# secon_analog_in.net
KiCad netlist of a schematic drawn in Altium Designer
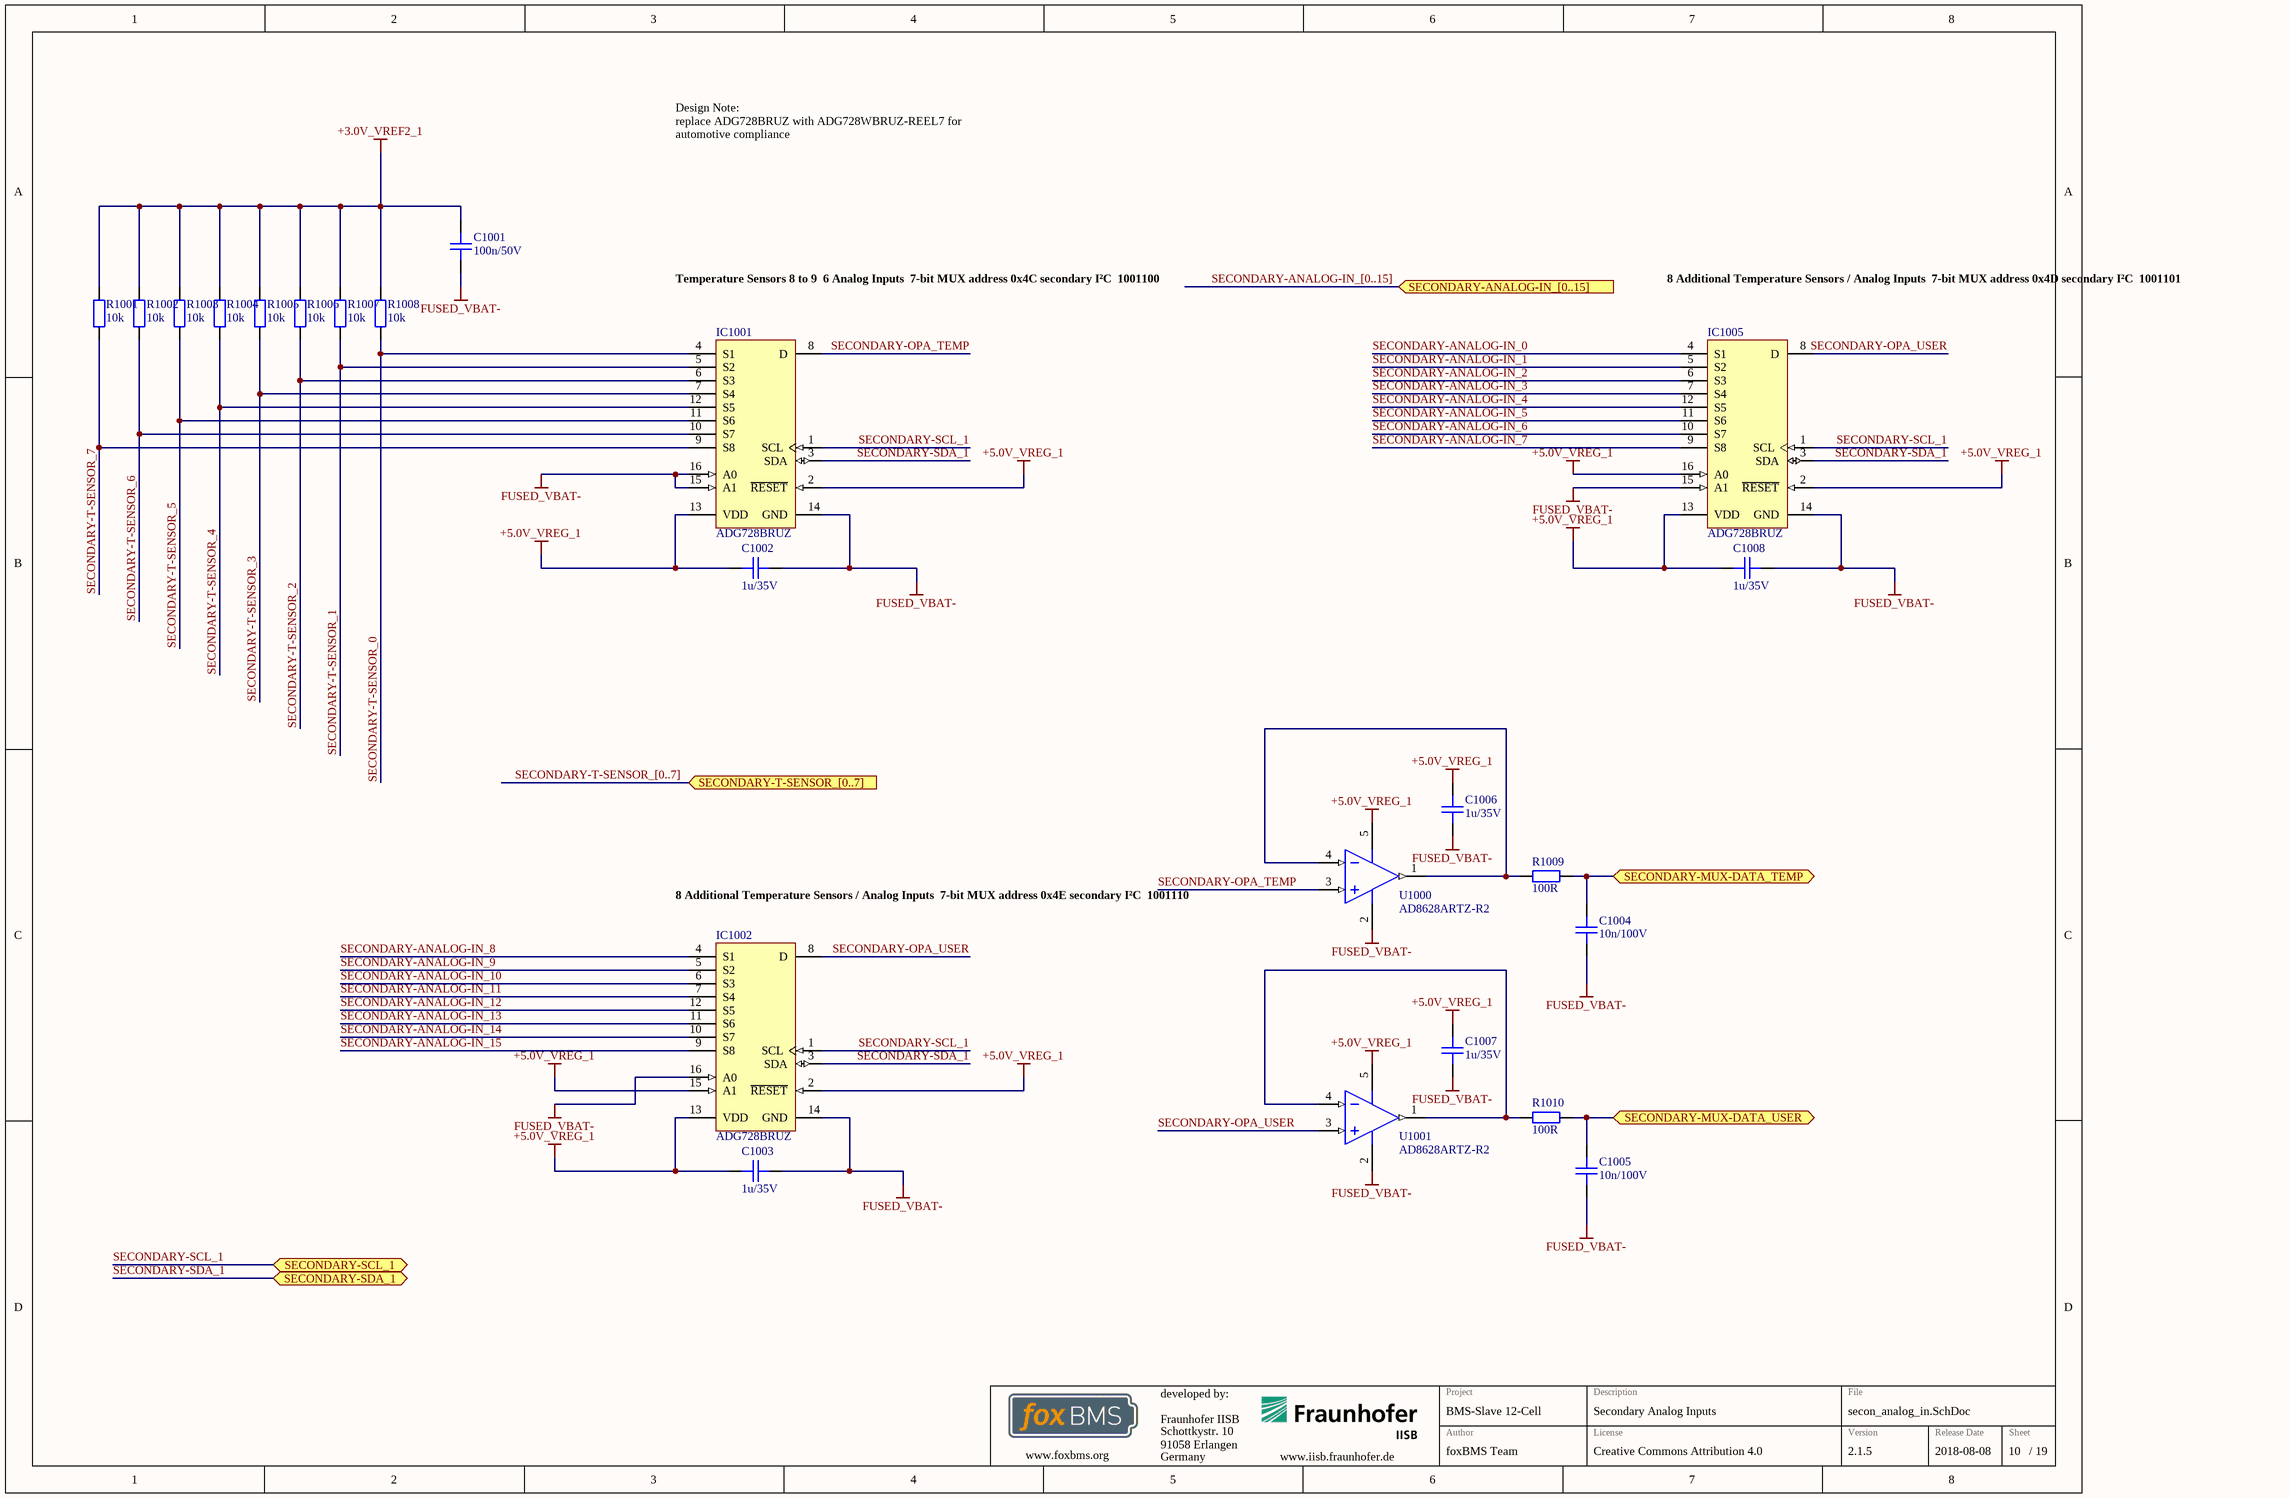
[diagram p0: secon_analog_in.SchDoc]

(export (version "E")
  (design (tool "Eeschema 10.0.6"))
  (components
    (comp (ref "C1001")
      (value "100n/50V")
      (footprint "CAPC1608X08N")
      (description "MLCC")
      (fields (field (name "PART NUMBER") "gen_C_ceramic_100n_50V_X7R_0603"))
      (libsource (lib "OE750") (part "C"))
    )
    (comp (ref "C1002")
      (value "1u/35V")
      (footprint "CAPC1608X08N")
      (description "MLCC")
      (fields (field (name "PART NUMBER") "gen_C_ceramic_1u_35V_X7R_0603"))
      (libsource (lib "OE750") (part "C"))
    )
    (comp (ref "C1003")
      (value "1u/35V")
      (footprint "CAPC1608X08N")
      (description "MLCC")
      (fields (field (name "PART NUMBER") "gen_C_ceramic_1u_35V_X7R_0603"))
      (libsource (lib "OE750") (part "C"))
    )
    (comp (ref "C1004")
      (value "10n/100V")
      (footprint "CAPC1608X08N")
      (description "MLCC")
      (fields (field (name "PART NUMBER") "gen_C_ceramic_10n_100V_X7R_0603"))
      (libsource (lib "OE750") (part "C"))
    )
    (comp (ref "C1005")
      (value "10n/100V")
      (footprint "CAPC1608X08N")
      (description "MLCC")
      (fields (field (name "PART NUMBER") "gen_C_ceramic_10n_100V_X7R_0603"))
      (libsource (lib "OE750") (part "C"))
    )
    (comp (ref "C1006")
      (value "1u/35V")
      (footprint "CAPC1608X08N")
      (description "MLCC")
      (fields (field (name "PART NUMBER") "gen_C_ceramic_1u_35V_X7R_0603"))
      (libsource (lib "OE750") (part "C"))
    )
    (comp (ref "C1007")
      (value "1u/35V")
      (footprint "CAPC1608X08N")
      (description "MLCC")
      (fields (field (name "PART NUMBER") "gen_C_ceramic_1u_35V_X7R_0603"))
      (libsource (lib "OE750") (part "C"))
    )
    (comp (ref "C1008")
      (value "1u/35V")
      (footprint "CAPC1608X08N")
      (description "MLCC")
      (fields (field (name "PART NUMBER") "gen_C_ceramic_1u_35V_X7R_0603"))
      (libsource (lib "OE750") (part "C"))
    )
    (comp (ref "IC1001")
      (value "ADG728BRUZ")
      (footprint "ADI-RU-16_M")
      (fields (field (name "MANUFACTURER") "Analog Devices"))
      (libsource (lib "Altium Content Vault") (part "ADI-ADG728-RU-16"))
    )
    (comp (ref "IC1002")
      (value "ADG728BRUZ")
      (footprint "ADI-RU-16_M")
      (fields (field (name "MANUFACTURER") "Analog Devices"))
      (libsource (lib "Altium Content Vault") (part "ADI-ADG728-RU-16"))
    )
    (comp (ref "IC1005")
      (value "ADG728BRUZ")
      (footprint "ADI-RU-16_M")
      (fields (field (name "MANUFACTURER") "Analog Devices"))
      (libsource (lib "Altium Content Vault") (part "ADI-ADG728-RU-16"))
    )
    (comp (ref "R1001")
      (value "10k")
      (footprint "RESC1608X05N")
      (description "SMD Resistor 10k 0603")
      (fields (field (name "PART NUMBER") "gen_R_10k_0603") (field (name "TOLERANCE") "1%"))
      (libsource (lib "OE750") (part "R"))
    )
    (comp (ref "R1002")
      (value "10k")
      (footprint "RESC1608X05N")
      (description "SMD Resistor 10k 0603")
      (fields (field (name "PART NUMBER") "gen_R_10k_0603") (field (name "TOLERANCE") "1%"))
      (libsource (lib "OE750") (part "R"))
    )
    (comp (ref "R1003")
      (value "10k")
      (footprint "RESC1608X05N")
      (description "SMD Resistor 10k 0603")
      (fields (field (name "PART NUMBER") "gen_R_10k_0603") (field (name "TOLERANCE") "1%"))
      (libsource (lib "OE750") (part "R"))
    )
    (comp (ref "R1004")
      (value "10k")
      (footprint "RESC1608X05N")
      (description "SMD Resistor 10k 0603")
      (fields (field (name "PART NUMBER") "gen_R_10k_0603") (field (name "TOLERANCE") "1%"))
      (libsource (lib "OE750") (part "R"))
    )
    (comp (ref "R1005")
      (value "10k")
      (footprint "RESC1608X05N")
      (description "SMD Resistor 10k 0603")
      (fields (field (name "PART NUMBER") "gen_R_10k_0603") (field (name "TOLERANCE") "1%"))
      (libsource (lib "OE750") (part "R"))
    )
    (comp (ref "R1006")
      (value "10k")
      (footprint "RESC1608X05N")
      (description "SMD Resistor 10k 0603")
      (fields (field (name "PART NUMBER") "gen_R_10k_0603") (field (name "TOLERANCE") "1%"))
      (libsource (lib "OE750") (part "R"))
    )
    (comp (ref "R1007")
      (value "10k")
      (footprint "RESC1608X05N")
      (description "SMD Resistor 10k 0603")
      (fields (field (name "PART NUMBER") "gen_R_10k_0603") (field (name "TOLERANCE") "1%"))
      (libsource (lib "OE750") (part "R"))
    )
    (comp (ref "R1008")
      (value "10k")
      (footprint "RESC1608X05N")
      (description "SMD Resistor 10k 0603")
      (fields (field (name "PART NUMBER") "gen_R_10k_0603") (field (name "TOLERANCE") "1%"))
      (libsource (lib "OE750") (part "R"))
    )
    (comp (ref "R1009")
      (value "100R")
      (footprint "RESC1608X05N")
      (description "SMD Resistor 100R 0603")
      (fields (field (name "PART NUMBER") "gen_R_100R_0603") (field (name "TOLERANCE") "1%"))
      (libsource (lib "OE750") (part "R"))
    )
    (comp (ref "R1010")
      (value "100R")
      (footprint "RESC1608X05N")
      (description "SMD Resistor 100R 0603")
      (fields (field (name "PART NUMBER") "gen_R_100R_0603") (field (name "TOLERANCE") "1%"))
      (libsource (lib "OE750") (part "R"))
    )
    (comp (ref "U1000")
      (value "AD8628ARTZ-R2")
      (footprint "ADI-RJ-5_M")
      (fields (field (name "MANUFACTURER") "Analog Devices") (field (name "GENERIC PART NUMBER") "AD8628"))
      (libsource (lib "Altium Content Vault") (part "ADI-ADxxxx-X-5"))
    )
    (comp (ref "U1001")
      (value "AD8628ARTZ-R2")
      (footprint "ADI-RJ-5_M")
      (fields (field (name "MANUFACTURER") "Analog Devices") (field (name "GENERIC PART NUMBER") "AD8628"))
      (libsource (lib "Altium Content Vault") (part "ADI-ADxxxx-X-5"))
    )
  )
  (nets
    (net (code "1") (name "+3.0V_VREF2_1") (class "Default")
      (node (ref "C1001") (pin "2") (pinfunction "2_2") (pintype "passive"))
      (node (ref "R1001") (pin "2") (pinfunction "2_2") (pintype "passive"))
      (node (ref "R1002") (pin "2") (pinfunction "2_2") (pintype "passive"))
      (node (ref "R1003") (pin "2") (pinfunction "2_2") (pintype "passive"))
      (node (ref "R1004") (pin "2") (pinfunction "2_2") (pintype "passive"))
      (node (ref "R1005") (pin "2") (pinfunction "2_2") (pintype "passive"))
      (node (ref "R1006") (pin "2") (pinfunction "2_2") (pintype "passive"))
      (node (ref "R1007") (pin "2") (pinfunction "2_2") (pintype "passive"))
      (node (ref "R1008") (pin "2") (pinfunction "2_2") (pintype "passive"))
    )
    (net (code "2") (name "+5.0V_VREG_1") (class "Default")
      (node (ref "C1002") (pin "2") (pinfunction "2_2") (pintype "passive"))
      (node (ref "C1003") (pin "2") (pinfunction "2_2") (pintype "passive"))
      (node (ref "C1006") (pin "2") (pinfunction "2_2") (pintype "passive"))
      (node (ref "C1007") (pin "2") (pinfunction "2_2") (pintype "passive"))
      (node (ref "C1008") (pin "2") (pinfunction "2_2") (pintype "passive"))
      (node (ref "IC1001") (pin "13") (pinfunction "VDD_13") (pintype "power_in"))
      (node (ref "IC1001") (pin "2") (pinfunction "~{RESET}_2") (pintype "input"))
      (node (ref "IC1002") (pin "13") (pinfunction "VDD_13") (pintype "power_in"))
      (node (ref "IC1002") (pin "15") (pinfunction "A1_15") (pintype "input"))
      (node (ref "IC1002") (pin "2") (pinfunction "~{RESET}_2") (pintype "input"))
      (node (ref "IC1005") (pin "13") (pinfunction "VDD_13") (pintype "power_in"))
      (node (ref "IC1005") (pin "16") (pinfunction "A0_16") (pintype "input"))
      (node (ref "IC1005") (pin "2") (pinfunction "~{RESET}_2") (pintype "input"))
      (node (ref "U1000") (pin "5") (pinfunction "+V_5") (pintype "power_in"))
      (node (ref "U1001") (pin "5") (pinfunction "+V_5") (pintype "power_in"))
    )
    (net (code "3") (name "/SECONDARY-ANALOG-IN_0") (class "Default")
      (node (ref "IC1005") (pin "4") (pinfunction "S1_4") (pintype "passive"))
    )
    (net (code "4") (name "/SECONDARY-ANALOG-IN_1") (class "Default")
      (node (ref "IC1005") (pin "5") (pinfunction "S2_5") (pintype "passive"))
    )
    (net (code "5") (name "/SECONDARY-ANALOG-IN_2") (class "Default")
      (node (ref "IC1005") (pin "6") (pinfunction "S3_6") (pintype "passive"))
    )
    (net (code "6") (name "/SECONDARY-ANALOG-IN_3") (class "Default")
      (node (ref "IC1005") (pin "7") (pinfunction "S4_7") (pintype "passive"))
    )
    (net (code "7") (name "/SECONDARY-ANALOG-IN_4") (class "Default")
      (node (ref "IC1005") (pin "12") (pinfunction "S5_12") (pintype "passive"))
    )
    (net (code "8") (name "/SECONDARY-ANALOG-IN_5") (class "Default")
      (node (ref "IC1005") (pin "11") (pinfunction "S6_11") (pintype "passive"))
    )
    (net (code "9") (name "/SECONDARY-ANALOG-IN_6") (class "Default")
      (node (ref "IC1005") (pin "10") (pinfunction "S7_10") (pintype "passive"))
    )
    (net (code "10") (name "/SECONDARY-ANALOG-IN_7") (class "Default")
      (node (ref "IC1005") (pin "9") (pinfunction "S8_9") (pintype "passive"))
    )
    (net (code "11") (name "/SECONDARY-ANALOG-IN_8") (class "Default")
      (node (ref "IC1002") (pin "4") (pinfunction "S1_4") (pintype "passive"))
    )
    (net (code "12") (name "/SECONDARY-ANALOG-IN_9") (class "Default")
      (node (ref "IC1002") (pin "5") (pinfunction "S2_5") (pintype "passive"))
    )
    (net (code "13") (name "/SECONDARY-ANALOG-IN_10") (class "Default")
      (node (ref "IC1002") (pin "6") (pinfunction "S3_6") (pintype "passive"))
    )
    (net (code "14") (name "/SECONDARY-ANALOG-IN_11") (class "Default")
      (node (ref "IC1002") (pin "7") (pinfunction "S4_7") (pintype "passive"))
    )
    (net (code "15") (name "/SECONDARY-ANALOG-IN_12") (class "Default")
      (node (ref "IC1002") (pin "12") (pinfunction "S5_12") (pintype "passive"))
    )
    (net (code "16") (name "/SECONDARY-ANALOG-IN_13") (class "Default")
      (node (ref "IC1002") (pin "11") (pinfunction "S6_11") (pintype "passive"))
    )
    (net (code "17") (name "/SECONDARY-ANALOG-IN_14") (class "Default")
      (node (ref "IC1002") (pin "10") (pinfunction "S7_10") (pintype "passive"))
    )
    (net (code "18") (name "/SECONDARY-ANALOG-IN_15") (class "Default")
      (node (ref "IC1002") (pin "9") (pinfunction "S8_9") (pintype "passive"))
    )
    (net (code "20") (name "/SECONDARY-MUX-DATA_TEMP") (class "Default")
      (node (ref "C1004") (pin "2") (pinfunction "2_2") (pintype "passive"))
      (node (ref "R1009") (pin "2") (pinfunction "2_2") (pintype "passive"))
    )
    (net (code "21") (name "/SECONDARY-MUX-DATA_USER") (class "Default")
      (node (ref "C1005") (pin "2") (pinfunction "2_2") (pintype "passive"))
      (node (ref "R1010") (pin "2") (pinfunction "2_2") (pintype "passive"))
    )
    (net (code "22") (name "/SECONDARY-OPA_TEMP") (class "Default")
      (node (ref "IC1001") (pin "8") (pinfunction "D_8") (pintype "passive"))
      (node (ref "U1000") (pin "3") (pinfunction "+IN_3") (pintype "input"))
    )
    (net (code "23") (name "/SECONDARY-OPA_USER") (class "Default")
      (node (ref "IC1002") (pin "8") (pinfunction "D_8") (pintype "passive"))
      (node (ref "IC1005") (pin "8") (pinfunction "D_8") (pintype "passive"))
      (node (ref "U1001") (pin "3") (pinfunction "+IN_3") (pintype "input"))
    )
    (net (code "24") (name "/SECONDARY-SCL_1") (class "Default")
      (node (ref "IC1001") (pin "1") (pinfunction "SCL_1") (pintype "input"))
      (node (ref "IC1002") (pin "1") (pinfunction "SCL_1") (pintype "input"))
      (node (ref "IC1005") (pin "1") (pinfunction "SCL_1") (pintype "input"))
    )
    (net (code "25") (name "/SECONDARY-SDA_1") (class "Default")
      (node (ref "IC1001") (pin "3") (pinfunction "SDA_3") (pintype "bidirectional"))
      (node (ref "IC1002") (pin "3") (pinfunction "SDA_3") (pintype "bidirectional"))
      (node (ref "IC1005") (pin "3") (pinfunction "SDA_3") (pintype "bidirectional"))
    )
    (net (code "26") (name "/SECONDARY-T-SENSOR_0") (class "Default")
      (node (ref "IC1001") (pin "4") (pinfunction "S1_4") (pintype "passive"))
      (node (ref "R1008") (pin "1") (pinfunction "1_1") (pintype "passive"))
    )
    (net (code "27") (name "/SECONDARY-T-SENSOR_1") (class "Default")
      (node (ref "IC1001") (pin "5") (pinfunction "S2_5") (pintype "passive"))
      (node (ref "R1007") (pin "1") (pinfunction "1_1") (pintype "passive"))
    )
    (net (code "28") (name "/SECONDARY-T-SENSOR_2") (class "Default")
      (node (ref "IC1001") (pin "6") (pinfunction "S3_6") (pintype "passive"))
      (node (ref "R1006") (pin "1") (pinfunction "1_1") (pintype "passive"))
    )
    (net (code "29") (name "/SECONDARY-T-SENSOR_3") (class "Default")
      (node (ref "IC1001") (pin "7") (pinfunction "S4_7") (pintype "passive"))
      (node (ref "R1005") (pin "1") (pinfunction "1_1") (pintype "passive"))
    )
    (net (code "30") (name "/SECONDARY-T-SENSOR_4") (class "Default")
      (node (ref "IC1001") (pin "12") (pinfunction "S5_12") (pintype "passive"))
      (node (ref "R1004") (pin "1") (pinfunction "1_1") (pintype "passive"))
    )
    (net (code "31") (name "/SECONDARY-T-SENSOR_5") (class "Default")
      (node (ref "IC1001") (pin "11") (pinfunction "S6_11") (pintype "passive"))
      (node (ref "R1003") (pin "1") (pinfunction "1_1") (pintype "passive"))
    )
    (net (code "32") (name "/SECONDARY-T-SENSOR_6") (class "Default")
      (node (ref "IC1001") (pin "10") (pinfunction "S7_10") (pintype "passive"))
      (node (ref "R1002") (pin "1") (pinfunction "1_1") (pintype "passive"))
    )
    (net (code "33") (name "/SECONDARY-T-SENSOR_7") (class "Default")
      (node (ref "IC1001") (pin "9") (pinfunction "S8_9") (pintype "passive"))
      (node (ref "R1001") (pin "1") (pinfunction "1_1") (pintype "passive"))
    )
    (net (code "35") (name "FUSED_VBAT-") (class "Default")
      (node (ref "C1001") (pin "1") (pinfunction "1_1") (pintype "passive"))
      (node (ref "C1002") (pin "1") (pinfunction "1_1") (pintype "passive"))
      (node (ref "C1003") (pin "1") (pinfunction "1_1") (pintype "passive"))
      (node (ref "C1004") (pin "1") (pinfunction "1_1") (pintype "passive"))
      (node (ref "C1005") (pin "1") (pinfunction "1_1") (pintype "passive"))
      (node (ref "C1006") (pin "1") (pinfunction "1_1") (pintype "passive"))
      (node (ref "C1007") (pin "1") (pinfunction "1_1") (pintype "passive"))
      (node (ref "C1008") (pin "1") (pinfunction "1_1") (pintype "passive"))
      (node (ref "IC1001") (pin "14") (pinfunction "GND_14") (pintype "power_in"))
      (node (ref "IC1001") (pin "15") (pinfunction "A1_15") (pintype "input"))
      (node (ref "IC1001") (pin "16") (pinfunction "A0_16") (pintype "input"))
      (node (ref "IC1002") (pin "14") (pinfunction "GND_14") (pintype "power_in"))
      (node (ref "IC1002") (pin "16") (pinfunction "A0_16") (pintype "input"))
      (node (ref "IC1005") (pin "14") (pinfunction "GND_14") (pintype "power_in"))
      (node (ref "IC1005") (pin "15") (pinfunction "A1_15") (pintype "input"))
      (node (ref "U1000") (pin "2") (pinfunction "-V_2") (pintype "power_in"))
      (node (ref "U1001") (pin "2") (pinfunction "-V_2") (pintype "power_in"))
    )
    (net (code "36") (name "Net-(U1000--IN)") (class "Default")
      (node (ref "R1009") (pin "1") (pinfunction "1_1") (pintype "passive"))
      (node (ref "U1000") (pin "1") (pinfunction "OUT_1") (pintype "output"))
      (node (ref "U1000") (pin "4") (pinfunction "-IN_4") (pintype "input"))
    )
    (net (code "37") (name "Net-(U1001--IN)") (class "Default")
      (node (ref "R1010") (pin "1") (pinfunction "1_1") (pintype "passive"))
      (node (ref "U1001") (pin "1") (pinfunction "OUT_1") (pintype "output"))
      (node (ref "U1001") (pin "4") (pinfunction "-IN_4") (pintype "input"))
    )
  )
)
